# Serializer.net
KiCad netlist of a schematic drawn in Altium Designer
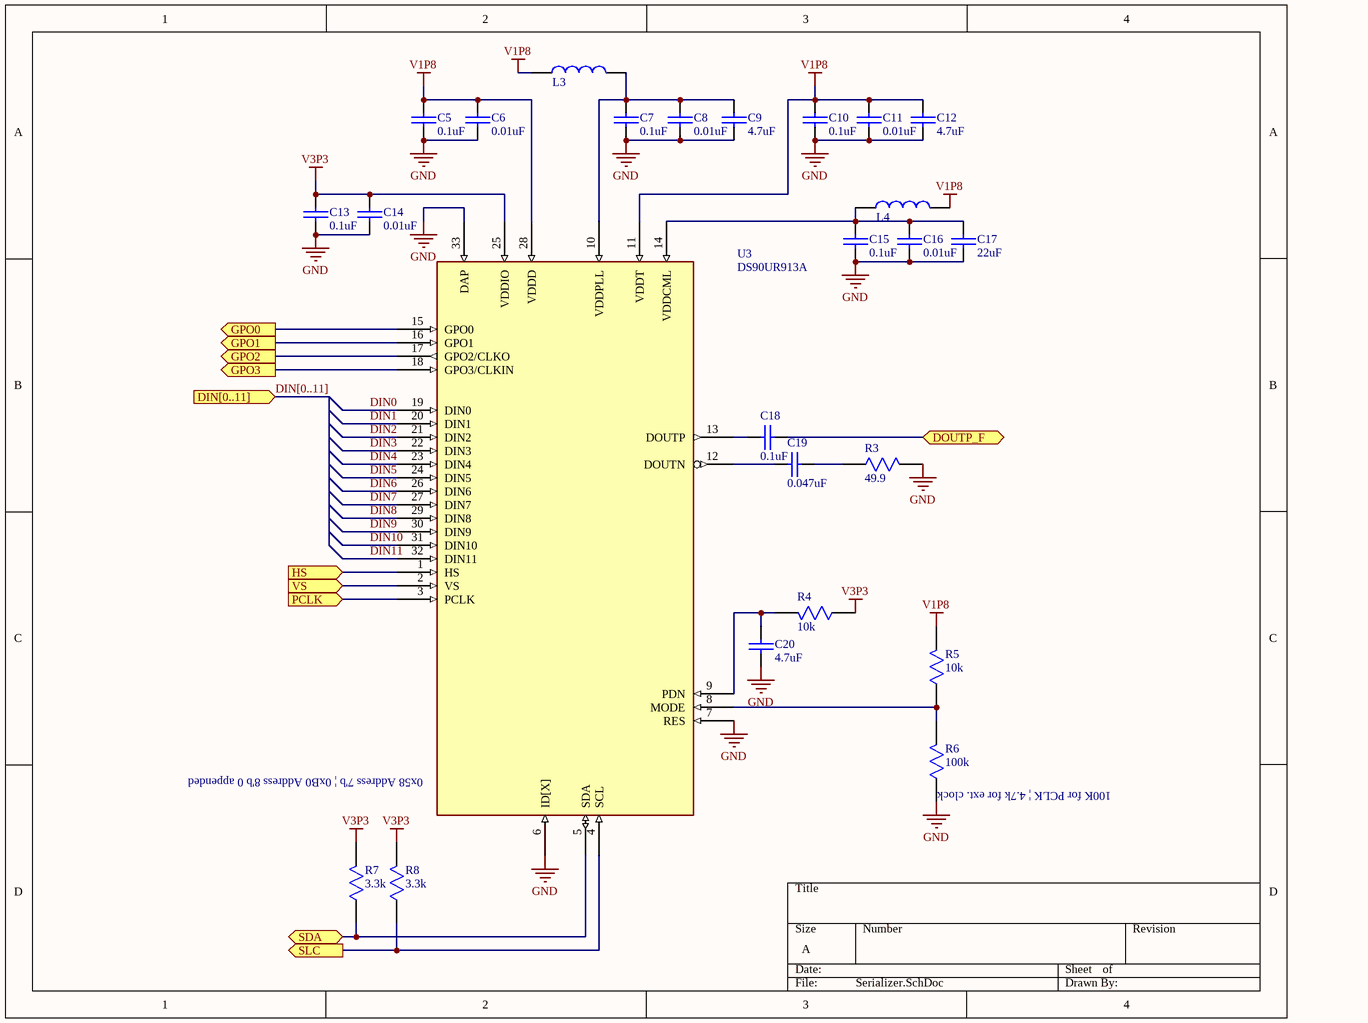
[diagram p0: Serializer.SchDoc]

(export (version "E")
  (design (tool "Eeschema 10.0.6"))
  (components
    (comp (ref "C5")
      (value "0.1uF")
      (footprint "SMD CAP 0402")
      (libsource (lib "DA_Component_Library") (part "Capacitor"))
    )
    (comp (ref "C6")
      (value "0.01uF")
      (footprint "SMD CAP 0402")
      (libsource (lib "DA_Component_Library") (part "Capacitor"))
    )
    (comp (ref "C7")
      (value "0.1uF")
      (footprint "SMD CAP 0402")
      (libsource (lib "DA_Component_Library") (part "Capacitor"))
    )
    (comp (ref "C8")
      (value "0.01uF")
      (footprint "SMD CAP 0402")
      (libsource (lib "DA_Component_Library") (part "Capacitor"))
    )
    (comp (ref "C9")
      (value "4.7uF")
      (footprint "SMD CAP 0402")
      (libsource (lib "DA_Component_Library") (part "Capacitor"))
    )
    (comp (ref "C10")
      (value "0.1uF")
      (footprint "SMD CAP 0402")
      (libsource (lib "DA_Component_Library") (part "Capacitor"))
    )
    (comp (ref "C11")
      (value "0.01uF")
      (footprint "SMD CAP 0402")
      (libsource (lib "DA_Component_Library") (part "Capacitor"))
    )
    (comp (ref "C12")
      (value "4.7uF")
      (footprint "SMD CAP 0402")
      (libsource (lib "DA_Component_Library") (part "Capacitor"))
    )
    (comp (ref "C13")
      (value "0.1uF")
      (footprint "SMD CAP 0402")
      (libsource (lib "DA_Component_Library") (part "Capacitor"))
    )
    (comp (ref "C14")
      (value "0.01uF")
      (footprint "SMD CAP 0402")
      (libsource (lib "DA_Component_Library") (part "Capacitor"))
    )
    (comp (ref "C15")
      (value "0.1uF")
      (footprint "SMD CAP 0402")
      (libsource (lib "DA_Component_Library") (part "Capacitor"))
    )
    (comp (ref "C16")
      (value "0.01uF")
      (footprint "SMD CAP 0402")
      (libsource (lib "DA_Component_Library") (part "Capacitor"))
    )
    (comp (ref "C17")
      (value "22uF")
      (footprint "SMD Capacitor 0603")
      (libsource (lib "DA_Component_Library") (part "Capacitor"))
    )
    (comp (ref "C18")
      (value "0.1uF")
      (footprint "SMD CAP 0402")
      (libsource (lib "DA_Component_Library") (part "Capacitor"))
    )
    (comp (ref "C19")
      (value "0.047uF")
      (footprint "SMD CAP 0402")
      (libsource (lib "DA_Component_Library") (part "Capacitor"))
    )
    (comp (ref "C20")
      (value "4.7uF")
      (footprint "SMD CAP 0402")
      (libsource (lib "DA_Component_Library") (part "Capacitor"))
    )
    (comp (ref "L3")
      (value "Ferrite Bead")
      (footprint "BLM18KG601SN1D")
      (libsource (lib "DA_Component_Library") (part "Ferrite Bead"))
    )
    (comp (ref "L4")
      (value "Ferrite Bead")
      (footprint "BLM18KG601SN1D")
      (libsource (lib "DA_Component_Library") (part "Ferrite Bead"))
    )
    (comp (ref "R3")
      (value "49.9")
      (footprint "SMD RES 0402")
      (libsource (lib "DA_Component_Library") (part "Resistor"))
    )
    (comp (ref "R4")
      (value "10k")
      (footprint "SMD RES 0402")
      (libsource (lib "DA_Component_Library") (part "Resistor"))
    )
    (comp (ref "R5")
      (value "10k")
      (footprint "SMD RES 0402")
      (libsource (lib "DA_Component_Library") (part "Resistor"))
    )
    (comp (ref "R6")
      (value "100k")
      (footprint "SMD RES 0402")
      (libsource (lib "DA_Component_Library") (part "Resistor"))
    )
    (comp (ref "R7")
      (value "3.3k")
      (footprint "SMD RES 0402")
      (libsource (lib "DA_Component_Library") (part "Resistor"))
    )
    (comp (ref "R8")
      (value "3.3k")
      (footprint "SMD RES 0402")
      (libsource (lib "DA_Component_Library") (part "Resistor"))
    )
    (comp (ref "U3")
      (value "DS90UR913A")
      (footprint "WQFN32 for DS90UB913A")
      (description "DS90UR913ASERIALIZER")
      (libsource (lib "DA_Component_Library") (part "DS90UR913A"))
    )
  )
  (nets
    (net (code "1") (name "/DIN0") (class "Default")
      (node (ref "U3") (pin "19") (pinfunction "DIN0_19") (pintype "input"))
    )
    (net (code "2") (name "/DIN1") (class "Default")
      (node (ref "U3") (pin "20") (pinfunction "DIN1_20") (pintype "input"))
    )
    (net (code "3") (name "/DIN2") (class "Default")
      (node (ref "U3") (pin "21") (pinfunction "DIN2_21") (pintype "input"))
    )
    (net (code "4") (name "/DIN3") (class "Default")
      (node (ref "U3") (pin "22") (pinfunction "DIN3_22") (pintype "input"))
    )
    (net (code "5") (name "/DIN4") (class "Default")
      (node (ref "U3") (pin "23") (pinfunction "DIN4_23") (pintype "input"))
    )
    (net (code "6") (name "/DIN5") (class "Default")
      (node (ref "U3") (pin "24") (pinfunction "DIN5_24") (pintype "input"))
    )
    (net (code "7") (name "/DIN6") (class "Default")
      (node (ref "U3") (pin "26") (pinfunction "DIN6_26") (pintype "input"))
    )
    (net (code "8") (name "/DIN7") (class "Default")
      (node (ref "U3") (pin "27") (pinfunction "DIN7_27") (pintype "input"))
    )
    (net (code "9") (name "/DIN8") (class "Default")
      (node (ref "U3") (pin "29") (pinfunction "DIN8_29") (pintype "input"))
    )
    (net (code "10") (name "/DIN9") (class "Default")
      (node (ref "U3") (pin "30") (pinfunction "DIN9_30") (pintype "input"))
    )
    (net (code "11") (name "/DIN10") (class "Default")
      (node (ref "U3") (pin "31") (pinfunction "DIN10_31") (pintype "input"))
    )
    (net (code "12") (name "/DIN11") (class "Default")
      (node (ref "U3") (pin "32") (pinfunction "DIN11_32") (pintype "input"))
    )
    (net (code "14") (name "/DOUTP_F") (class "Default")
      (node (ref "C18") (pin "1") (pinfunction "1_1") (pintype "passive"))
    )
    (net (code "15") (name "/GPO0") (class "Default")
      (node (ref "U3") (pin "15") (pinfunction "GPO0_15") (pintype "input"))
    )
    (net (code "16") (name "/GPO1") (class "Default")
      (node (ref "U3") (pin "16") (pinfunction "GPO1_16") (pintype "input"))
    )
    (net (code "17") (name "/GPO2") (class "Default")
      (node (ref "U3") (pin "17") (pinfunction "GPO2/CLKO_17") (pintype "output"))
    )
    (net (code "18") (name "/GPO3") (class "Default")
      (node (ref "U3") (pin "18") (pinfunction "GPO3/CLKIN_18") (pintype "input"))
    )
    (net (code "19") (name "/HS") (class "Default")
      (node (ref "U3") (pin "1") (pinfunction "HS_1") (pintype "input"))
    )
    (net (code "20") (name "/PCLK") (class "Default")
      (node (ref "U3") (pin "3") (pinfunction "PCLK_3") (pintype "input"))
    )
    (net (code "21") (name "/SDA") (class "Default")
      (node (ref "R7") (pin "0") (pinfunction "0_0") (pintype "passive"))
      (node (ref "U3") (pin "5") (pinfunction "SDA_5") (pintype "bidirectional"))
    )
    (net (code "22") (name "/SLC") (class "Default")
      (node (ref "R8") (pin "0") (pinfunction "0_0") (pintype "passive"))
      (node (ref "U3") (pin "4") (pinfunction "SCL_4") (pintype "input"))
    )
    (net (code "23") (name "/VS") (class "Default")
      (node (ref "U3") (pin "2") (pinfunction "VS_2") (pintype "input"))
    )
    (net (code "24") (name "GND") (class "Default")
      (node (ref "C10") (pin "1") (pinfunction "1_1") (pintype "passive"))
      (node (ref "C11") (pin "1") (pinfunction "1_1") (pintype "passive"))
      (node (ref "C12") (pin "1") (pinfunction "1_1") (pintype "passive"))
      (node (ref "C13") (pin "1") (pinfunction "1_1") (pintype "passive"))
      (node (ref "C14") (pin "1") (pinfunction "1_1") (pintype "passive"))
      (node (ref "C15") (pin "1") (pinfunction "1_1") (pintype "passive"))
      (node (ref "C16") (pin "1") (pinfunction "1_1") (pintype "passive"))
      (node (ref "C17") (pin "1") (pinfunction "1_1") (pintype "passive"))
      (node (ref "C20") (pin "1") (pinfunction "1_1") (pintype "passive"))
      (node (ref "C5") (pin "1") (pinfunction "1_1") (pintype "passive"))
      (node (ref "C6") (pin "1") (pinfunction "1_1") (pintype "passive"))
      (node (ref "C7") (pin "1") (pinfunction "1_1") (pintype "passive"))
      (node (ref "C8") (pin "1") (pinfunction "1_1") (pintype "passive"))
      (node (ref "C9") (pin "1") (pinfunction "1_1") (pintype "passive"))
      (node (ref "R3") (pin "1") (pinfunction "1_1") (pintype "passive"))
      (node (ref "R6") (pin "0") (pinfunction "0_0") (pintype "passive"))
      (node (ref "U3") (pin "33") (pinfunction "DAP_33") (pintype "input"))
      (node (ref "U3") (pin "6") (pinfunction "ID[X]_6") (pintype "input"))
      (node (ref "U3") (pin "7") (pinfunction "RES_7") (pintype "input"))
    )
    (net (code "25") (name "Net-(C19-Pad1)") (class "Default")
      (node (ref "C19") (pin "1") (pinfunction "1_1") (pintype "passive"))
      (node (ref "R3") (pin "0") (pinfunction "0_0") (pintype "passive"))
    )
    (net (code "26") (name "Net-(U3-DOUTN)") (class "Default")
      (node (ref "C19") (pin "0") (pinfunction "0_0") (pintype "passive"))
      (node (ref "U3") (pin "12") (pinfunction "DOUTN_12") (pintype "output"))
    )
    (net (code "27") (name "Net-(U3-DOUTP)") (class "Default")
      (node (ref "C18") (pin "0") (pinfunction "0_0") (pintype "passive"))
      (node (ref "U3") (pin "13") (pinfunction "DOUTP_13") (pintype "output"))
    )
    (net (code "28") (name "Net-(U3-MODE)") (class "Default")
      (node (ref "R5") (pin "0") (pinfunction "0_0") (pintype "passive"))
      (node (ref "R6") (pin "1") (pinfunction "1_1") (pintype "passive"))
      (node (ref "U3") (pin "8") (pinfunction "MODE_8") (pintype "input"))
    )
    (net (code "29") (name "Net-(U3-PDN)") (class "Default")
      (node (ref "C20") (pin "0") (pinfunction "0_0") (pintype "passive"))
      (node (ref "R4") (pin "1") (pinfunction "1_1") (pintype "passive"))
      (node (ref "U3") (pin "9") (pinfunction "PDN_9") (pintype "input"))
    )
    (net (code "30") (name "Net-(U3-VDDCML)") (class "Default")
      (node (ref "C15") (pin "0") (pinfunction "0_0") (pintype "passive"))
      (node (ref "C16") (pin "0") (pinfunction "0_0") (pintype "passive"))
      (node (ref "C17") (pin "0") (pinfunction "0_0") (pintype "passive"))
      (node (ref "L4") (pin "1") (pinfunction "1_1") (pintype "passive"))
      (node (ref "U3") (pin "14") (pinfunction "VDDCML_14") (pintype "input"))
    )
    (net (code "31") (name "Net-(U3-VDDPLL)") (class "Default")
      (node (ref "C7") (pin "0") (pinfunction "0_0") (pintype "passive"))
      (node (ref "C8") (pin "0") (pinfunction "0_0") (pintype "passive"))
      (node (ref "C9") (pin "0") (pinfunction "0_0") (pintype "passive"))
      (node (ref "L3") (pin "2") (pinfunction "2_2") (pintype "passive"))
      (node (ref "U3") (pin "10") (pinfunction "VDDPLL_10") (pintype "input"))
    )
    (net (code "32") (name "V1P8") (class "Default")
      (node (ref "C10") (pin "0") (pinfunction "0_0") (pintype "passive"))
      (node (ref "C11") (pin "0") (pinfunction "0_0") (pintype "passive"))
      (node (ref "C12") (pin "0") (pinfunction "0_0") (pintype "passive"))
      (node (ref "C5") (pin "0") (pinfunction "0_0") (pintype "passive"))
      (node (ref "C6") (pin "0") (pinfunction "0_0") (pintype "passive"))
      (node (ref "L3") (pin "1") (pinfunction "1_1") (pintype "passive"))
      (node (ref "L4") (pin "2") (pinfunction "2_2") (pintype "passive"))
      (node (ref "R5") (pin "1") (pinfunction "1_1") (pintype "passive"))
      (node (ref "U3") (pin "11") (pinfunction "VDDT_11") (pintype "input"))
      (node (ref "U3") (pin "28") (pinfunction "VDDD_28") (pintype "input"))
    )
    (net (code "33") (name "V3P3") (class "Default")
      (node (ref "C13") (pin "0") (pinfunction "0_0") (pintype "passive"))
      (node (ref "C14") (pin "0") (pinfunction "0_0") (pintype "passive"))
      (node (ref "R4") (pin "0") (pinfunction "0_0") (pintype "passive"))
      (node (ref "R7") (pin "1") (pinfunction "1_1") (pintype "passive"))
      (node (ref "R8") (pin "1") (pinfunction "1_1") (pintype "passive"))
      (node (ref "U3") (pin "25") (pinfunction "VDDIO_25") (pintype "input"))
    )
  )
)
